# CaravanPi_V2.net
KiCad netlist of a schematic drawn in EAGLE
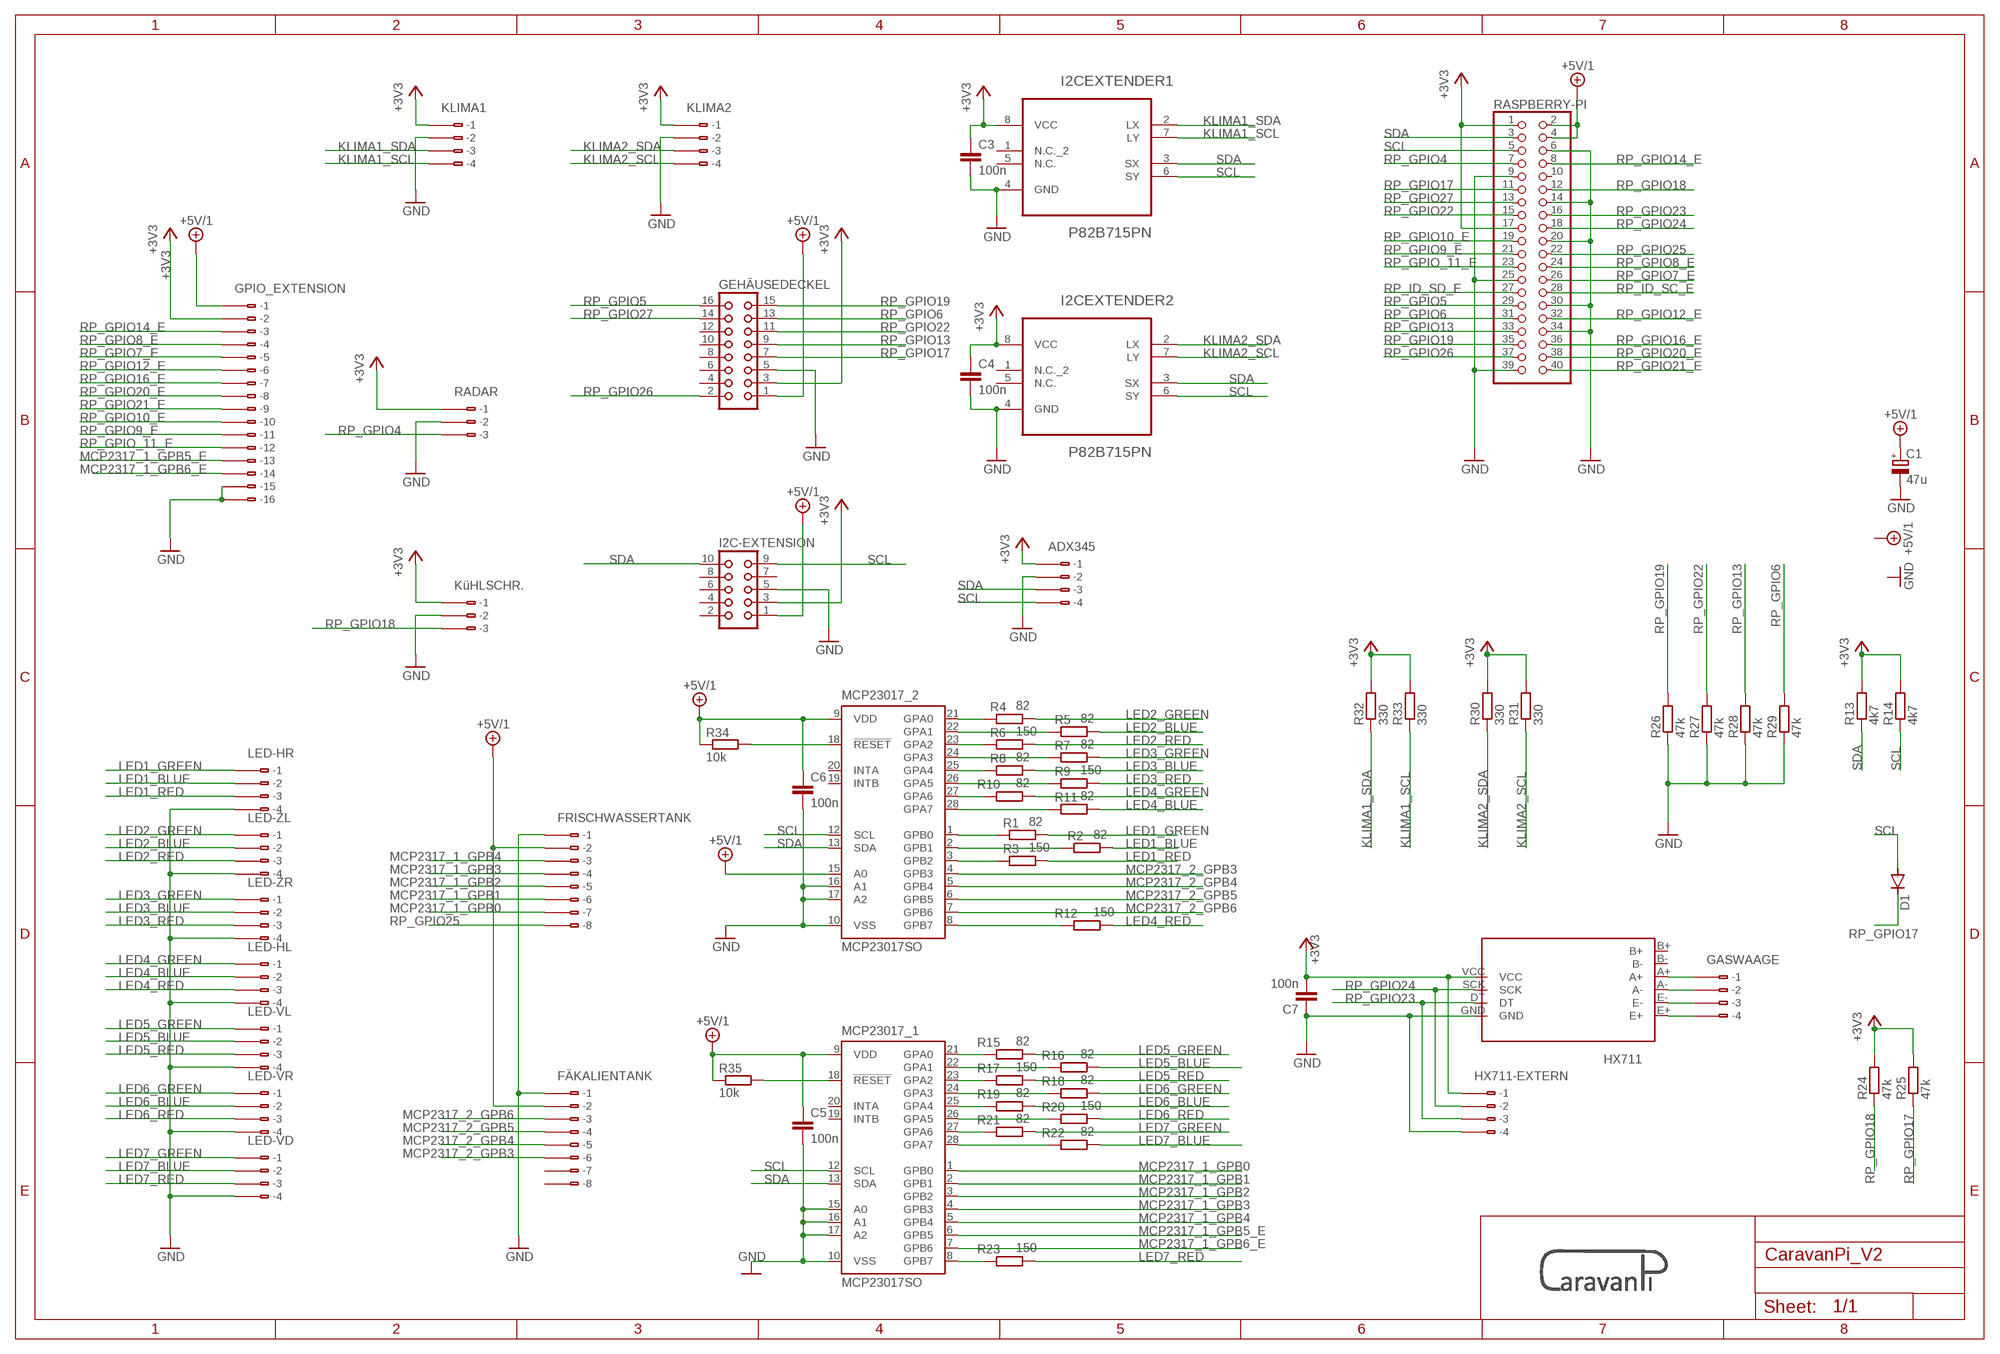
[diagram p0: schematic, sheet 1]

(export (version "E")
  (design (tool "Eeschema 10.0.6"))
  (components
    (comp (ref "ADX345")
      (value "233-404")
      (footprint "eagle-import:233-404")
      (libsource (lib "eagle-import") (part "233-404"))
    )
    (comp (ref "C1")
      (value "47u")
      (footprint "eagle-import:SMC_C")
      (libsource (lib "eagle-import") (part "CPOL-EUSMCC"))
    )
    (comp (ref "C3")
      (value "100n")
      (footprint "eagle-import:C1206")
      (libsource (lib "eagle-import") (part "C-EUC1206"))
    )
    (comp (ref "C4")
      (value "100n")
      (footprint "eagle-import:C1206")
      (libsource (lib "eagle-import") (part "C-EUC1206"))
    )
    (comp (ref "C5")
      (value "100n")
      (footprint "eagle-import:C1206")
      (libsource (lib "eagle-import") (part "C-EUC1206"))
    )
    (comp (ref "C6")
      (value "100n")
      (footprint "eagle-import:C1206")
      (libsource (lib "eagle-import") (part "C-EUC1206"))
    )
    (comp (ref "C7")
      (value "100n")
      (footprint "eagle-import:C1206")
      (libsource (lib "eagle-import") (part "C-EUC1206"))
    )
    (comp (ref "D1")
      (value "DIODE-DO214AC")
      (footprint "eagle-import:DO214AC")
      (libsource (lib "eagle-import") (part "DIODE-DO214AC"))
    )
    (comp (ref "FRISCHWASSERTANK")
      (value "233-408")
      (footprint "eagle-import:233-408")
      (libsource (lib "eagle-import") (part "233-408"))
    )
    (comp (ref "FÄKALIENTANK")
      (value "233-408")
      (footprint "eagle-import:233-408")
      (libsource (lib "eagle-import") (part "233-408"))
    )
    (comp (ref "GASWAAGE")
      (value "233-404")
      (footprint "eagle-import:233-404")
      (libsource (lib "eagle-import") (part "233-404"))
    )
    (comp (ref "GEHÄUSEDECKEL")
      (value "CON16")
      (footprint "eagle-import:CON16")
      (libsource (lib "eagle-import") (part "CON16"))
    )
    (comp (ref "GPIO_EXTENSION")
      (value "233-516")
      (footprint "eagle-import:233-516")
      (fields (field (name "MF") "Wago Corporation") (field (name "MPN") "0233-0516"))
      (libsource (lib "eagle-import") (part "233-516"))
    )
    (comp (ref "HX711")
      (value "HX711A")
      (footprint "eagle-import:HX711")
      (libsource (lib "eagle-import") (part "HX711A"))
    )
    (comp (ref "HX711-EXTERN")
      (value "233-404")
      (footprint "eagle-import:233-404")
      (libsource (lib "eagle-import") (part "233-404"))
    )
    (comp (ref "I2C-EXTENSION")
      (value "CON10")
      (footprint "eagle-import:CON10")
      (libsource (lib "eagle-import") (part "CON10"))
    )
    (comp (ref "I2CEXTENDER1")
      (value "P82B715PN")
      (footprint "eagle-import:DIP254P762X420-8")
      (libsource (lib "eagle-import") (part "P82B715PN"))
    )
    (comp (ref "I2CEXTENDER2")
      (value "P82B715PN")
      (footprint "eagle-import:DIP254P762X420-8")
      (libsource (lib "eagle-import") (part "P82B715PN"))
    )
    (comp (ref "KLIMA1")
      (value "233-404")
      (footprint "eagle-import:233-404")
      (libsource (lib "eagle-import") (part "233-404"))
    )
    (comp (ref "KLIMA2")
      (value "233-404")
      (footprint "eagle-import:233-404")
      (libsource (lib "eagle-import") (part "233-404"))
    )
    (comp (ref "KüHLSCHR.")
      (value "233-403")
      (footprint "eagle-import:233-403")
      (libsource (lib "eagle-import") (part "233-403"))
    )
    (comp (ref "LED-HL")
      (value "233-504")
      (footprint "eagle-import:233-504")
      (fields (field (name "MF") "Wago Corporation") (field (name "MPN") "0233-0504"))
      (libsource (lib "eagle-import") (part "233-504"))
    )
    (comp (ref "LED-HR")
      (value "233-504")
      (footprint "eagle-import:233-504")
      (fields (field (name "MF") "Wago Corporation") (field (name "MPN") "0233-0504"))
      (libsource (lib "eagle-import") (part "233-504"))
    )
    (comp (ref "LED-VD")
      (value "233-504")
      (footprint "eagle-import:233-504")
      (fields (field (name "MF") "Wago Corporation") (field (name "MPN") "0233-0504"))
      (libsource (lib "eagle-import") (part "233-504"))
    )
    (comp (ref "LED-VL")
      (value "233-504")
      (footprint "eagle-import:233-504")
      (fields (field (name "MF") "Wago Corporation") (field (name "MPN") "0233-0504"))
      (libsource (lib "eagle-import") (part "233-504"))
    )
    (comp (ref "LED-VR")
      (value "233-504")
      (footprint "eagle-import:233-504")
      (fields (field (name "MF") "Wago Corporation") (field (name "MPN") "0233-0504"))
      (libsource (lib "eagle-import") (part "233-504"))
    )
    (comp (ref "LED-ZL")
      (value "233-504")
      (footprint "eagle-import:233-504")
      (fields (field (name "MF") "Wago Corporation") (field (name "MPN") "0233-0504"))
      (libsource (lib "eagle-import") (part "233-504"))
    )
    (comp (ref "LED-ZR")
      (value "233-504")
      (footprint "eagle-import:233-504")
      (fields (field (name "MF") "Wago Corporation") (field (name "MPN") "0233-0504"))
      (libsource (lib "eagle-import") (part "233-504"))
    )
    (comp (ref "MCP23017_1")
      (value "MCP23017SO")
      (footprint "eagle-import:SO28W")
      (libsource (lib "eagle-import") (part "MCP23017SO"))
    )
    (comp (ref "MCP23017_2")
      (value "MCP23017SO")
      (footprint "eagle-import:SO28W")
      (libsource (lib "eagle-import") (part "MCP23017SO"))
    )
    (comp (ref "R1")
      (value "82")
      (footprint "eagle-import:M1206")
      (libsource (lib "eagle-import") (part "R-EU_M1206"))
    )
    (comp (ref "R2")
      (value "82")
      (footprint "eagle-import:M1206")
      (libsource (lib "eagle-import") (part "R-EU_M1206"))
    )
    (comp (ref "R3")
      (value "150")
      (footprint "eagle-import:M1206")
      (libsource (lib "eagle-import") (part "R-EU_M1206"))
    )
    (comp (ref "R4")
      (value "82")
      (footprint "eagle-import:M1206")
      (libsource (lib "eagle-import") (part "R-EU_M1206"))
    )
    (comp (ref "R5")
      (value "82")
      (footprint "eagle-import:M1206")
      (libsource (lib "eagle-import") (part "R-EU_M1206"))
    )
    (comp (ref "R6")
      (value "150")
      (footprint "eagle-import:M1206")
      (libsource (lib "eagle-import") (part "R-EU_M1206"))
    )
    (comp (ref "R7")
      (value "82")
      (footprint "eagle-import:M1206")
      (libsource (lib "eagle-import") (part "R-EU_M1206"))
    )
    (comp (ref "R8")
      (value "82")
      (footprint "eagle-import:M1206")
      (libsource (lib "eagle-import") (part "R-EU_M1206"))
    )
    (comp (ref "R9")
      (value "150")
      (footprint "eagle-import:M1206")
      (libsource (lib "eagle-import") (part "R-EU_M1206"))
    )
    (comp (ref "R10")
      (value "82")
      (footprint "eagle-import:M1206")
      (libsource (lib "eagle-import") (part "R-EU_M1206"))
    )
    (comp (ref "R11")
      (value "82")
      (footprint "eagle-import:M1206")
      (libsource (lib "eagle-import") (part "R-EU_M1206"))
    )
    (comp (ref "R12")
      (value "150")
      (footprint "eagle-import:M1206")
      (libsource (lib "eagle-import") (part "R-EU_M1206"))
    )
    (comp (ref "R13")
      (value "4k7")
      (footprint "eagle-import:M1206")
      (libsource (lib "eagle-import") (part "R-EU_M1206"))
    )
    (comp (ref "R14")
      (value "4k7")
      (footprint "eagle-import:M1206")
      (libsource (lib "eagle-import") (part "R-EU_M1206"))
    )
    (comp (ref "R15")
      (value "82")
      (footprint "eagle-import:M1206")
      (libsource (lib "eagle-import") (part "R-EU_M1206"))
    )
    (comp (ref "R16")
      (value "82")
      (footprint "eagle-import:M1206")
      (libsource (lib "eagle-import") (part "R-EU_M1206"))
    )
    (comp (ref "R17")
      (value "150")
      (footprint "eagle-import:M1206")
      (libsource (lib "eagle-import") (part "R-EU_M1206"))
    )
    (comp (ref "R18")
      (value "82")
      (footprint "eagle-import:M1206")
      (libsource (lib "eagle-import") (part "R-EU_M1206"))
    )
    (comp (ref "R19")
      (value "82")
      (footprint "eagle-import:M1206")
      (libsource (lib "eagle-import") (part "R-EU_M1206"))
    )
    (comp (ref "R20")
      (value "150")
      (footprint "eagle-import:M1206")
      (libsource (lib "eagle-import") (part "R-EU_M1206"))
    )
    (comp (ref "R21")
      (value "82")
      (footprint "eagle-import:M1206")
      (libsource (lib "eagle-import") (part "R-EU_M1206"))
    )
    (comp (ref "R22")
      (value "82")
      (footprint "eagle-import:M1206")
      (libsource (lib "eagle-import") (part "R-EU_M1206"))
    )
    (comp (ref "R23")
      (value "150")
      (footprint "eagle-import:M1206")
      (libsource (lib "eagle-import") (part "R-EU_M1206"))
    )
    (comp (ref "R24")
      (value "47k")
      (footprint "eagle-import:M1206")
      (libsource (lib "eagle-import") (part "R-EU_M1206"))
    )
    (comp (ref "R25")
      (value "47k")
      (footprint "eagle-import:M1206")
      (libsource (lib "eagle-import") (part "R-EU_M1206"))
    )
    (comp (ref "R26")
      (value "47k")
      (footprint "eagle-import:M1206")
      (libsource (lib "eagle-import") (part "R-EU_M1206"))
    )
    (comp (ref "R27")
      (value "47k")
      (footprint "eagle-import:M1206")
      (libsource (lib "eagle-import") (part "R-EU_M1206"))
    )
    (comp (ref "R28")
      (value "47k")
      (footprint "eagle-import:M1206")
      (libsource (lib "eagle-import") (part "R-EU_M1206"))
    )
    (comp (ref "R29")
      (value "47k")
      (footprint "eagle-import:M1206")
      (libsource (lib "eagle-import") (part "R-EU_M1206"))
    )
    (comp (ref "R30")
      (value "330")
      (footprint "eagle-import:M1206")
      (libsource (lib "eagle-import") (part "R-EU_M1206"))
    )
    (comp (ref "R31")
      (value "330")
      (footprint "eagle-import:M1206")
      (libsource (lib "eagle-import") (part "R-EU_M1206"))
    )
    (comp (ref "R32")
      (value "330")
      (footprint "eagle-import:M1206")
      (libsource (lib "eagle-import") (part "R-EU_M1206"))
    )
    (comp (ref "R33")
      (value "330")
      (footprint "eagle-import:M1206")
      (libsource (lib "eagle-import") (part "R-EU_M1206"))
    )
    (comp (ref "R34")
      (value "10k")
      (footprint "eagle-import:M1206")
      (libsource (lib "eagle-import") (part "R-EU_M1206"))
    )
    (comp (ref "R35")
      (value "10k")
      (footprint "eagle-import:M1206")
      (libsource (lib "eagle-import") (part "R-EU_M1206"))
    )
    (comp (ref "RADAR")
      (value "233-403")
      (footprint "eagle-import:233-403")
      (libsource (lib "eagle-import") (part "233-403"))
    )
    (comp (ref "RASPBERRY-PI")
      (value "PINHD-2X20")
      (footprint "eagle-import:2X20")
      (libsource (lib "eagle-import") (part "PINHD-2X20"))
    )
    (comp (ref "U$1")
      (value "CARAVAN_PI_LOGO")
      (footprint "eagle-import:CARAVAN_PI_LOGO")
      (libsource (lib "eagle-import") (part "CARAVAN_PI_LOGO"))
    )
  )
  (nets
    (net (code "1") (name "+3V3") (class "Default")
      (node (ref "ADX345") (pin "B1") (pinfunction "B-1_B1") (pintype "passive"))
      (node (ref "C3") (pin "1") (pinfunction "1_1") (pintype "passive"))
      (node (ref "C4") (pin "1") (pinfunction "1_1") (pintype "passive"))
      (node (ref "C7") (pin "2") (pinfunction "2_2") (pintype "passive"))
      (node (ref "GEHÄUSEDECKEL") (pin "3") (pinfunction "3_3") (pintype "passive"))
      (node (ref "GPIO_EXTENSION") (pin "B2") (pinfunction "B-2_B2") (pintype "passive"))
      (node (ref "HX711") (pin "VCC") (pinfunction "VCC_VCC") (pintype "bidirectional"))
      (node (ref "HX711-EXTERN") (pin "B1") (pinfunction "B-1_B1") (pintype "passive"))
      (node (ref "I2C-EXTENSION") (pin "3") (pinfunction "3_3") (pintype "passive"))
      (node (ref "I2CEXTENDER1") (pin "8") (pinfunction "VCC_8") (pintype "power_in"))
      (node (ref "I2CEXTENDER2") (pin "8") (pinfunction "VCC_8") (pintype "power_in"))
      (node (ref "KLIMA1") (pin "B1") (pinfunction "B-1_B1") (pintype "passive"))
      (node (ref "KLIMA2") (pin "B1") (pinfunction "B-1_B1") (pintype "passive"))
      (node (ref "KüHLSCHR.") (pin "B1") (pinfunction "B-1_B1") (pintype "passive"))
      (node (ref "R13") (pin "2") (pinfunction "2_2") (pintype "passive"))
      (node (ref "R14") (pin "2") (pinfunction "2_2") (pintype "passive"))
      (node (ref "R24") (pin "2") (pinfunction "2_2") (pintype "passive"))
      (node (ref "R25") (pin "2") (pinfunction "2_2") (pintype "passive"))
      (node (ref "R30") (pin "2") (pinfunction "2_2") (pintype "passive"))
      (node (ref "R31") (pin "2") (pinfunction "2_2") (pintype "passive"))
      (node (ref "R32") (pin "2") (pinfunction "2_2") (pintype "passive"))
      (node (ref "R33") (pin "2") (pinfunction "2_2") (pintype "passive"))
      (node (ref "RADAR") (pin "B1") (pinfunction "B-1_B1") (pintype "passive"))
      (node (ref "RASPBERRY-PI") (pin "1") (pinfunction "1_1") (pintype "passive"))
      (node (ref "RASPBERRY-PI") (pin "17") (pinfunction "17_17") (pintype "passive"))
    )
    (net (code "2") (name "+5V{slash}1") (class "Default")
      (node (ref "C1") (pin "+") (pinfunction "+_+") (pintype "passive"))
      (node (ref "C5") (pin "1") (pinfunction "1_1") (pintype "passive"))
      (node (ref "C6") (pin "1") (pinfunction "1_1") (pintype "passive"))
      (node (ref "FRISCHWASSERTANK") (pin "B2") (pinfunction "B-2_B2") (pintype "passive"))
      (node (ref "FÄKALIENTANK") (pin "B2") (pinfunction "B-2_B2") (pintype "passive"))
      (node (ref "GEHÄUSEDECKEL") (pin "1") (pinfunction "1_1") (pintype "passive"))
      (node (ref "GPIO_EXTENSION") (pin "B1") (pinfunction "B-1_B1") (pintype "passive"))
      (node (ref "I2C-EXTENSION") (pin "1") (pinfunction "1_1") (pintype "passive"))
      (node (ref "MCP23017_1") (pin "9") (pinfunction "VDD_9") (pintype "power_in"))
      (node (ref "MCP23017_2") (pin "15") (pinfunction "A0_15") (pintype "input"))
      (node (ref "MCP23017_2") (pin "9") (pinfunction "VDD_9") (pintype "power_in"))
      (node (ref "R34") (pin "1") (pinfunction "1_1") (pintype "passive"))
      (node (ref "R35") (pin "1") (pinfunction "1_1") (pintype "passive"))
      (node (ref "RASPBERRY-PI") (pin "2") (pinfunction "2_2") (pintype "passive"))
      (node (ref "RASPBERRY-PI") (pin "4") (pinfunction "4_4") (pintype "passive"))
    )
    (net (code "3") (name "/KLIMA1_SCL") (class "Default")
      (node (ref "I2CEXTENDER1") (pin "7") (pinfunction "LY_7") (pintype "bidirectional"))
      (node (ref "KLIMA1") (pin "B4") (pinfunction "B-4_B4") (pintype "passive"))
      (node (ref "R33") (pin "1") (pinfunction "1_1") (pintype "passive"))
    )
    (net (code "4") (name "/KLIMA1_SDA") (class "Default")
      (node (ref "I2CEXTENDER1") (pin "2") (pinfunction "LX_2") (pintype "bidirectional"))
      (node (ref "KLIMA1") (pin "B3") (pinfunction "B-3_B3") (pintype "passive"))
      (node (ref "R32") (pin "1") (pinfunction "1_1") (pintype "passive"))
    )
    (net (code "5") (name "/KLIMA2_SCL") (class "Default")
      (node (ref "I2CEXTENDER2") (pin "7") (pinfunction "LY_7") (pintype "bidirectional"))
      (node (ref "KLIMA2") (pin "B4") (pinfunction "B-4_B4") (pintype "passive"))
      (node (ref "R31") (pin "1") (pinfunction "1_1") (pintype "passive"))
    )
    (net (code "6") (name "/KLIMA2_SDA") (class "Default")
      (node (ref "I2CEXTENDER2") (pin "2") (pinfunction "LX_2") (pintype "bidirectional"))
      (node (ref "KLIMA2") (pin "B3") (pinfunction "B-3_B3") (pintype "passive"))
      (node (ref "R30") (pin "1") (pinfunction "1_1") (pintype "passive"))
    )
    (net (code "7") (name "/LED1_BLUE") (class "Default")
      (node (ref "LED-HR") (pin "B2") (pinfunction "B-2_B2") (pintype "passive"))
      (node (ref "R2") (pin "2") (pinfunction "2_2") (pintype "passive"))
    )
    (net (code "8") (name "/LED1_GREEN") (class "Default")
      (node (ref "LED-HR") (pin "B1") (pinfunction "B-1_B1") (pintype "passive"))
      (node (ref "R1") (pin "2") (pinfunction "2_2") (pintype "passive"))
    )
    (net (code "9") (name "/LED1_RED") (class "Default")
      (node (ref "LED-HR") (pin "B3") (pinfunction "B-3_B3") (pintype "passive"))
      (node (ref "R3") (pin "2") (pinfunction "2_2") (pintype "passive"))
    )
    (net (code "10") (name "/LED2_BLUE") (class "Default")
      (node (ref "LED-ZL") (pin "B2") (pinfunction "B-2_B2") (pintype "passive"))
      (node (ref "R5") (pin "2") (pinfunction "2_2") (pintype "passive"))
    )
    (net (code "11") (name "/LED2_GREEN") (class "Default")
      (node (ref "LED-ZL") (pin "B1") (pinfunction "B-1_B1") (pintype "passive"))
      (node (ref "R4") (pin "2") (pinfunction "2_2") (pintype "passive"))
    )
    (net (code "12") (name "/LED2_RED") (class "Default")
      (node (ref "LED-ZL") (pin "B3") (pinfunction "B-3_B3") (pintype "passive"))
      (node (ref "R6") (pin "2") (pinfunction "2_2") (pintype "passive"))
    )
    (net (code "13") (name "/LED3_BLUE") (class "Default")
      (node (ref "LED-ZR") (pin "B2") (pinfunction "B-2_B2") (pintype "passive"))
      (node (ref "R8") (pin "2") (pinfunction "2_2") (pintype "passive"))
    )
    (net (code "14") (name "/LED3_GREEN") (class "Default")
      (node (ref "LED-ZR") (pin "B1") (pinfunction "B-1_B1") (pintype "passive"))
      (node (ref "R7") (pin "2") (pinfunction "2_2") (pintype "passive"))
    )
    (net (code "15") (name "/LED3_RED") (class "Default")
      (node (ref "LED-ZR") (pin "B3") (pinfunction "B-3_B3") (pintype "passive"))
      (node (ref "R9") (pin "2") (pinfunction "2_2") (pintype "passive"))
    )
    (net (code "16") (name "/LED4_BLUE") (class "Default")
      (node (ref "LED-HL") (pin "B2") (pinfunction "B-2_B2") (pintype "passive"))
      (node (ref "R11") (pin "2") (pinfunction "2_2") (pintype "passive"))
    )
    (net (code "17") (name "/LED4_GREEN") (class "Default")
      (node (ref "LED-HL") (pin "B1") (pinfunction "B-1_B1") (pintype "passive"))
      (node (ref "R10") (pin "2") (pinfunction "2_2") (pintype "passive"))
    )
    (net (code "18") (name "/LED4_RED") (class "Default")
      (node (ref "LED-HL") (pin "B3") (pinfunction "B-3_B3") (pintype "passive"))
      (node (ref "R12") (pin "2") (pinfunction "2_2") (pintype "passive"))
    )
    (net (code "19") (name "/LED5_BLUE") (class "Default")
      (node (ref "LED-VL") (pin "B2") (pinfunction "B-2_B2") (pintype "passive"))
      (node (ref "R16") (pin "2") (pinfunction "2_2") (pintype "passive"))
    )
    (net (code "20") (name "/LED5_GREEN") (class "Default")
      (node (ref "LED-VL") (pin "B1") (pinfunction "B-1_B1") (pintype "passive"))
      (node (ref "R15") (pin "2") (pinfunction "2_2") (pintype "passive"))
    )
    (net (code "21") (name "/LED5_RED") (class "Default")
      (node (ref "LED-VL") (pin "B3") (pinfunction "B-3_B3") (pintype "passive"))
      (node (ref "R17") (pin "2") (pinfunction "2_2") (pintype "passive"))
    )
    (net (code "22") (name "/LED6_BLUE") (class "Default")
      (node (ref "LED-VR") (pin "B2") (pinfunction "B-2_B2") (pintype "passive"))
      (node (ref "R19") (pin "2") (pinfunction "2_2") (pintype "passive"))
    )
    (net (code "23") (name "/LED6_GREEN") (class "Default")
      (node (ref "LED-VR") (pin "B1") (pinfunction "B-1_B1") (pintype "passive"))
      (node (ref "R18") (pin "2") (pinfunction "2_2") (pintype "passive"))
    )
    (net (code "24") (name "/LED6_RED") (class "Default")
      (node (ref "LED-VR") (pin "B3") (pinfunction "B-3_B3") (pintype "passive"))
      (node (ref "R20") (pin "2") (pinfunction "2_2") (pintype "passive"))
    )
    (net (code "25") (name "/LED7_BLUE") (class "Default")
      (node (ref "LED-VD") (pin "B2") (pinfunction "B-2_B2") (pintype "passive"))
      (node (ref "R22") (pin "2") (pinfunction "2_2") (pintype "passive"))
    )
    (net (code "26") (name "/LED7_GREEN") (class "Default")
      (node (ref "LED-VD") (pin "B1") (pinfunction "B-1_B1") (pintype "passive"))
      (node (ref "R21") (pin "2") (pinfunction "2_2") (pintype "passive"))
    )
    (net (code "27") (name "/LED7_RED") (class "Default")
      (node (ref "LED-VD") (pin "B3") (pinfunction "B-3_B3") (pintype "passive"))
      (node (ref "R23") (pin "2") (pinfunction "2_2") (pintype "passive"))
    )
    (net (code "28") (name "/MCP2317_1_GPB0") (class "Default")
      (node (ref "FRISCHWASSERTANK") (pin "B7") (pinfunction "B-7_B7") (pintype "passive"))
      (node (ref "MCP23017_1") (pin "1") (pinfunction "GPB0_1") (pintype "bidirectional"))
    )
    (net (code "29") (name "/MCP2317_1_GPB1") (class "Default")
      (node (ref "FRISCHWASSERTANK") (pin "B6") (pinfunction "B-6_B6") (pintype "passive"))
      (node (ref "MCP23017_1") (pin "2") (pinfunction "GPB1_2") (pintype "bidirectional"))
    )
    (net (code "30") (name "/MCP2317_1_GPB2") (class "Default")
      (node (ref "FRISCHWASSERTANK") (pin "B5") (pinfunction "B-5_B5") (pintype "passive"))
      (node (ref "MCP23017_1") (pin "3") (pinfunction "GPB2_3") (pintype "bidirectional"))
    )
    (net (code "31") (name "/MCP2317_1_GPB3") (class "Default")
      (node (ref "FRISCHWASSERTANK") (pin "B4") (pinfunction "B-4_B4") (pintype "passive"))
      (node (ref "MCP23017_1") (pin "4") (pinfunction "GPB3_4") (pintype "bidirectional"))
    )
    (net (code "32") (name "/MCP2317_1_GPB4") (class "Default")
      (node (ref "FRISCHWASSERTANK") (pin "B3") (pinfunction "B-3_B3") (pintype "passive"))
      (node (ref "MCP23017_1") (pin "5") (pinfunction "GPB4_5") (pintype "bidirectional"))
    )
    (net (code "33") (name "/MCP2317_1_GPB5_E") (class "Default")
      (node (ref "GPIO_EXTENSION") (pin "B13") (pinfunction "B-13_B13") (pintype "passive"))
      (node (ref "MCP23017_1") (pin "6") (pinfunction "GPB5_6") (pintype "bidirectional"))
    )
    (net (code "34") (name "/MCP2317_1_GPB6_E") (class "Default")
      (node (ref "GPIO_EXTENSION") (pin "B14") (pinfunction "B-14_B14") (pintype "passive"))
      (node (ref "MCP23017_1") (pin "7") (pinfunction "GPB6_7") (pintype "bidirectional"))
    )
    (net (code "35") (name "/MCP2317_2_GPB3") (class "Default")
      (node (ref "FÄKALIENTANK") (pin "B6") (pinfunction "B-6_B6") (pintype "passive"))
      (node (ref "MCP23017_2") (pin "4") (pinfunction "GPB3_4") (pintype "bidirectional"))
    )
    (net (code "36") (name "/MCP2317_2_GPB4") (class "Default")
      (node (ref "FÄKALIENTANK") (pin "B5") (pinfunction "B-5_B5") (pintype "passive"))
      (node (ref "MCP23017_2") (pin "5") (pinfunction "GPB4_5") (pintype "bidirectional"))
    )
    (net (code "37") (name "/MCP2317_2_GPB5") (class "Default")
      (node (ref "FÄKALIENTANK") (pin "B4") (pinfunction "B-4_B4") (pintype "passive"))
      (node (ref "MCP23017_2") (pin "6") (pinfunction "GPB5_6") (pintype "bidirectional"))
    )
    (net (code "38") (name "/MCP2317_2_GPB6") (class "Default")
      (node (ref "FÄKALIENTANK") (pin "B3") (pinfunction "B-3_B3") (pintype "passive"))
      (node (ref "MCP23017_2") (pin "7") (pinfunction "GPB6_7") (pintype "bidirectional"))
    )
    (net (code "39") (name "/RP_GPIO4") (class "Default")
      (node (ref "RADAR") (pin "B3") (pinfunction "B-3_B3") (pintype "passive"))
      (node (ref "RASPBERRY-PI") (pin "7") (pinfunction "7_7") (pintype "passive"))
    )
    (net (code "40") (name "/RP_GPIO5") (class "Default")
      (node (ref "GEHÄUSEDECKEL") (pin "16") (pinfunction "16_16") (pintype "passive"))
      (node (ref "RASPBERRY-PI") (pin "29") (pinfunction "29_29") (pintype "passive"))
    )
    (net (code "41") (name "/RP_GPIO6") (class "Default")
      (node (ref "GEHÄUSEDECKEL") (pin "13") (pinfunction "13_13") (pintype "passive"))
      (node (ref "R29") (pin "2") (pinfunction "2_2") (pintype "passive"))
      (node (ref "RASPBERRY-PI") (pin "31") (pinfunction "31_31") (pintype "passive"))
    )
    (net (code "42") (name "/RP_GPIO7_E") (class "Default")
      (node (ref "GPIO_EXTENSION") (pin "B5") (pinfunction "B-5_B5") (pintype "passive"))
      (node (ref "RASPBERRY-PI") (pin "26") (pinfunction "26_26") (pintype "passive"))
    )
    (net (code "43") (name "/RP_GPIO8_E") (class "Default")
      (node (ref "GPIO_EXTENSION") (pin "B4") (pinfunction "B-4_B4") (pintype "passive"))
      (node (ref "RASPBERRY-PI") (pin "24") (pinfunction "24_24") (pintype "passive"))
    )
    (net (code "44") (name "/RP_GPIO9_E") (class "Default")
      (node (ref "GPIO_EXTENSION") (pin "B11") (pinfunction "B-11_B11") (pintype "passive"))
      (node (ref "RASPBERRY-PI") (pin "21") (pinfunction "21_21") (pintype "passive"))
    )
    (net (code "45") (name "/RP_GPIO10_E") (class "Default")
      (node (ref "GPIO_EXTENSION") (pin "B10") (pinfunction "B-10_B10") (pintype "passive"))
      (node (ref "RASPBERRY-PI") (pin "19") (pinfunction "19_19") (pintype "passive"))
    )
    (net (code "46") (name "/RP_GPIO12_E") (class "Default")
      (node (ref "GPIO_EXTENSION") (pin "B6") (pinfunction "B-6_B6") (pintype "passive"))
      (node (ref "RASPBERRY-PI") (pin "32") (pinfunction "32_32") (pintype "passive"))
    )
    (net (code "47") (name "/RP_GPIO13") (class "Default")
      (node (ref "GEHÄUSEDECKEL") (pin "9") (pinfunction "9_9") (pintype "passive"))
      (node (ref "R28") (pin "2") (pinfunction "2_2") (pintype "passive"))
      (node (ref "RASPBERRY-PI") (pin "33") (pinfunction "33_33") (pintype "passive"))
    )
    (net (code "48") (name "/RP_GPIO14_E") (class "Default")
      (node (ref "GPIO_EXTENSION") (pin "B3") (pinfunction "B-3_B3") (pintype "passive"))
      (node (ref "RASPBERRY-PI") (pin "8") (pinfunction "8_8") (pintype "passive"))
    )
    (net (code "49") (name "/RP_GPIO16_E") (class "Default")
      (node (ref "GPIO_EXTENSION") (pin "B7") (pinfunction "B-7_B7") (pintype "passive"))
      (node (ref "RASPBERRY-PI") (pin "36") (pinfunction "36_36") (pintype "passive"))
    )
    (net (code "50") (name "/RP_GPIO17") (class "Default")
      (node (ref "D1") (pin "C") (pinfunction "C_C") (pintype "passive"))
      (node (ref "GEHÄUSEDECKEL") (pin "7") (pinfunction "7_7") (pintype "passive"))
      (node (ref "R25") (pin "1") (pinfunction "1_1") (pintype "passive"))
      (node (ref "RASPBERRY-PI") (pin "11") (pinfunction "11_11") (pintype "passive"))
    )
    (net (code "51") (name "/RP_GPIO18") (class "Default")
      (node (ref "KüHLSCHR.") (pin "B3") (pinfunction "B-3_B3") (pintype "passive"))
      (node (ref "R24") (pin "1") (pinfunction "1_1") (pintype "passive"))
      (node (ref "RASPBERRY-PI") (pin "12") (pinfunction "12_12") (pintype "passive"))
    )
    (net (code "52") (name "/RP_GPIO19") (class "Default")
      (node (ref "GEHÄUSEDECKEL") (pin "15") (pinfunction "15_15") (pintype "passive"))
      (node (ref "R26") (pin "2") (pinfunction "2_2") (pintype "passive"))
      (node (ref "RASPBERRY-PI") (pin "35") (pinfunction "35_35") (pintype "passive"))
    )
    (net (code "53") (name "/RP_GPIO20_E") (class "Default")
      (node (ref "GPIO_EXTENSION") (pin "B8") (pinfunction "B-8_B8") (pintype "passive"))
      (node (ref "RASPBERRY-PI") (pin "38") (pinfunction "38_38") (pintype "passive"))
    )
    (net (code "54") (name "/RP_GPIO21_E") (class "Default")
      (node (ref "GPIO_EXTENSION") (pin "B9") (pinfunction "B-9_B9") (pintype "passive"))
      (node (ref "RASPBERRY-PI") (pin "40") (pinfunction "40_40") (pintype "passive"))
    )
    (net (code "55") (name "/RP_GPIO22") (class "Default")
      (node (ref "GEHÄUSEDECKEL") (pin "11") (pinfunction "11_11") (pintype "passive"))
      (node (ref "R27") (pin "2") (pinfunction "2_2") (pintype "passive"))
      (node (ref "RASPBERRY-PI") (pin "15") (pinfunction "15_15") (pintype "passive"))
    )
    (net (code "56") (name "/RP_GPIO23") (class "Default")
      (node (ref "HX711") (pin "DT") (pinfunction "DT_DT") (pintype "bidirectional"))
      (node (ref "HX711-EXTERN") (pin "B3") (pinfunction "B-3_B3") (pintype "passive"))
      (node (ref "RASPBERRY-PI") (pin "16") (pinfunction "16_16") (pintype "passive"))
    )
    (net (code "57") (name "/RP_GPIO24") (class "Default")
      (node (ref "HX711") (pin "SCK") (pinfunction "SCK_SCK") (pintype "bidirectional"))
      (node (ref "HX711-EXTERN") (pin "B2") (pinfunction "B-2_B2") (pintype "passive"))
      (node (ref "RASPBERRY-PI") (pin "18") (pinfunction "18_18") (pintype "passive"))
    )
    (net (code "58") (name "/RP_GPIO25") (class "Default")
      (node (ref "FRISCHWASSERTANK") (pin "B8") (pinfunction "B-8_B8") (pintype "passive"))
      (node (ref "RASPBERRY-PI") (pin "22") (pinfunction "22_22") (pintype "passive"))
    )
    (net (code "59") (name "/RP_GPIO26") (class "Default")
      (node (ref "GEHÄUSEDECKEL") (pin "2") (pinfunction "2_2") (pintype "passive"))
      (node (ref "RASPBERRY-PI") (pin "37") (pinfunction "37_37") (pintype "passive"))
    )
    (net (code "60") (name "/RP_GPIO27") (class "Default")
      (node (ref "GEHÄUSEDECKEL") (pin "14") (pinfunction "14_14") (pintype "passive"))
      (node (ref "RASPBERRY-PI") (pin "13") (pinfunction "13_13") (pintype "passive"))
    )
    (net (code "61") (name "/RP_GPIO_11_E") (class "Default")
      (node (ref "GPIO_EXTENSION") (pin "B12") (pinfunction "B-12_B12") (pintype "passive"))
      (node (ref "RASPBERRY-PI") (pin "23") (pinfunction "23_23") (pintype "passive"))
    )
    (net (code "62") (name "/RP_ID_SC_E") (class "Default")
      (node (ref "RASPBERRY-PI") (pin "28") (pinfunction "28_28") (pintype "passive"))
    )
    (net (code "63") (name "/RP_ID_SD_E") (class "Default")
      (node (ref "RASPBERRY-PI") (pin "27") (pinfunction "27_27") (pintype "passive"))
    )
    (net (code "64") (name "/SCL") (class "Default")
      (node (ref "ADX345") (pin "B4") (pinfunction "B-4_B4") (pintype "passive"))
      (node (ref "D1") (pin "A") (pinfunction "A_A") (pintype "passive"))
      (node (ref "I2C-EXTENSION") (pin "9") (pinfunction "9_9") (pintype "passive"))
      (node (ref "I2CEXTENDER1") (pin "6") (pinfunction "SY_6") (pintype "bidirectional"))
      (node (ref "I2CEXTENDER2") (pin "6") (pinfunction "SY_6") (pintype "bidirectional"))
      (node (ref "MCP23017_1") (pin "12") (pinfunction "SCL_12") (pintype "input"))
      (node (ref "MCP23017_2") (pin "12") (pinfunction "SCL_12") (pintype "input"))
      (node (ref "R14") (pin "1") (pinfunction "1_1") (pintype "passive"))
      (node (ref "RASPBERRY-PI") (pin "5") (pinfunction "5_5") (pintype "passive"))
    )
    (net (code "65") (name "/SDA") (class "Default")
      (node (ref "ADX345") (pin "B3") (pinfunction "B-3_B3") (pintype "passive"))
      (node (ref "I2C-EXTENSION") (pin "10") (pinfunction "10_10") (pintype "passive"))
      (node (ref "I2CEXTENDER1") (pin "3") (pinfunction "SX_3") (pintype "bidirectional"))
      (node (ref "I2CEXTENDER2") (pin "3") (pinfunction "SX_3") (pintype "bidirectional"))
      (node (ref "MCP23017_1") (pin "13") (pinfunction "SDA_13") (pintype "bidirectional"))
      (node (ref "MCP23017_2") (pin "13") (pinfunction "SDA_13") (pintype "bidirectional"))
      (node (ref "R13") (pin "1") (pinfunction "1_1") (pintype "passive"))
      (node (ref "RASPBERRY-PI") (pin "3") (pinfunction "3_3") (pintype "passive"))
    )
    (net (code "66") (name "GND") (class "Default")
      (node (ref "ADX345") (pin "B2") (pinfunction "B-2_B2") (pintype "passive"))
      (node (ref "C1") (pin "-") (pinfunction "-_-") (pintype "passive"))
      (node (ref "C3") (pin "2") (pinfunction "2_2") (pintype "passive"))
      (node (ref "C4") (pin "2") (pinfunction "2_2") (pintype "passive"))
      (node (ref "C5") (pin "2") (pinfunction "2_2") (pintype "passive"))
      (node (ref "C6") (pin "2") (pinfunction "2_2") (pintype "passive"))
      (node (ref "C7") (pin "1") (pinfunction "1_1") (pintype "passive"))
      (node (ref "FRISCHWASSERTANK") (pin "B1") (pinfunction "B-1_B1") (pintype "passive"))
      (node (ref "FÄKALIENTANK") (pin "B1") (pinfunction "B-1_B1") (pintype "passive"))
      (node (ref "GEHÄUSEDECKEL") (pin "5") (pinfunction "5_5") (pintype "passive"))
      (node (ref "GPIO_EXTENSION") (pin "B15") (pinfunction "B-15_B15") (pintype "passive"))
      (node (ref "GPIO_EXTENSION") (pin "B16") (pinfunction "B-16_B16") (pintype "passive"))
      (node (ref "HX711") (pin "GND") (pinfunction "GND_GND") (pintype "bidirectional"))
      (node (ref "HX711-EXTERN") (pin "B4") (pinfunction "B-4_B4") (pintype "passive"))
      (node (ref "I2C-EXTENSION") (pin "5") (pinfunction "5_5") (pintype "passive"))
      (node (ref "I2CEXTENDER1") (pin "4") (pinfunction "GND_4") (pintype "passive"))
      (node (ref "I2CEXTENDER2") (pin "4") (pinfunction "GND_4") (pintype "passive"))
      (node (ref "KLIMA1") (pin "B2") (pinfunction "B-2_B2") (pintype "passive"))
      (node (ref "KLIMA2") (pin "B2") (pinfunction "B-2_B2") (pintype "passive"))
      (node (ref "KüHLSCHR.") (pin "B2") (pinfunction "B-2_B2") (pintype "passive"))
      (node (ref "LED-HL") (pin "B4") (pinfunction "B-4_B4") (pintype "passive"))
      (node (ref "LED-HR") (pin "B4") (pinfunction "B-4_B4") (pintype "passive"))
      (node (ref "LED-VD") (pin "B4") (pinfunction "B-4_B4") (pintype "passive"))
      (node (ref "LED-VL") (pin "B4") (pinfunction "B-4_B4") (pintype "passive"))
      (node (ref "LED-VR") (pin "B4") (pinfunction "B-4_B4") (pintype "passive"))
      (node (ref "LED-ZL") (pin "B4") (pinfunction "B-4_B4") (pintype "passive"))
      (node (ref "LED-ZR") (pin "B4") (pinfunction "B-4_B4") (pintype "passive"))
      (node (ref "MCP23017_1") (pin "10") (pinfunction "VSS_10") (pintype "power_in"))
      (node (ref "MCP23017_1") (pin "15") (pinfunction "A0_15") (pintype "input"))
      (node (ref "MCP23017_1") (pin "16") (pinfunction "A1_16") (pintype "input"))
      (node (ref "MCP23017_1") (pin "17") (pinfunction "A2_17") (pintype "input"))
      (node (ref "MCP23017_2") (pin "10") (pinfunction "VSS_10") (pintype "power_in"))
      (node (ref "MCP23017_2") (pin "16") (pinfunction "A1_16") (pintype "input"))
      (node (ref "MCP23017_2") (pin "17") (pinfunction "A2_17") (pintype "input"))
      (node (ref "R26") (pin "1") (pinfunction "1_1") (pintype "passive"))
      (node (ref "R27") (pin "1") (pinfunction "1_1") (pintype "passive"))
      (node (ref "R28") (pin "1") (pinfunction "1_1") (pintype "passive"))
      (node (ref "R29") (pin "1") (pinfunction "1_1") (pintype "passive"))
      (node (ref "RADAR") (pin "B2") (pinfunction "B-2_B2") (pintype "passive"))
      (node (ref "RASPBERRY-PI") (pin "14") (pinfunction "14_14") (pintype "passive"))
      (node (ref "RASPBERRY-PI") (pin "20") (pinfunction "20_20") (pintype "passive"))
      (node (ref "RASPBERRY-PI") (pin "25") (pinfunction "25_25") (pintype "passive"))
      (node (ref "RASPBERRY-PI") (pin "30") (pinfunction "30_30") (pintype "passive"))
      (node (ref "RASPBERRY-PI") (pin "34") (pinfunction "34_34") (pintype "passive"))
      (node (ref "RASPBERRY-PI") (pin "39") (pinfunction "39_39") (pintype "passive"))
      (node (ref "RASPBERRY-PI") (pin "6") (pinfunction "6_6") (pintype "passive"))
      (node (ref "RASPBERRY-PI") (pin "9") (pinfunction "9_9") (pintype "passive"))
    )
    (net (code "67") (name "Net-(GASWAAGE-B-1)") (class "Default")
      (node (ref "GASWAAGE") (pin "B1") (pinfunction "B-1_B1") (pintype "passive"))
      (node (ref "HX711") (pin "A+") (pinfunction "A+_A+") (pintype "bidirectional"))
    )
    (net (code "68") (name "Net-(GASWAAGE-B-2)") (class "Default")
      (node (ref "GASWAAGE") (pin "B2") (pinfunction "B-2_B2") (pintype "passive"))
      (node (ref "HX711") (pin "A-") (pinfunction "A-_A-") (pintype "bidirectional"))
    )
    (net (code "69") (name "Net-(GASWAAGE-B-3)") (class "Default")
      (node (ref "GASWAAGE") (pin "B3") (pinfunction "B-3_B3") (pintype "passive"))
      (node (ref "HX711") (pin "E-") (pinfunction "E-_E-") (pintype "bidirectional"))
    )
    (net (code "70") (name "Net-(GASWAAGE-B-4)") (class "Default")
      (node (ref "GASWAAGE") (pin "B4") (pinfunction "B-4_B4") (pintype "passive"))
      (node (ref "HX711") (pin "E+") (pinfunction "E+_E+") (pintype "bidirectional"))
    )
    (net (code "71") (name "Net-(MCP23017_1-GPA0)") (class "Default")
      (node (ref "MCP23017_1") (pin "21") (pinfunction "GPA0_21") (pintype "bidirectional"))
      (node (ref "R15") (pin "1") (pinfunction "1_1") (pintype "passive"))
    )
    (net (code "72") (name "Net-(MCP23017_1-GPA1)") (class "Default")
      (node (ref "MCP23017_1") (pin "22") (pinfunction "GPA1_22") (pintype "bidirectional"))
      (node (ref "R16") (pin "1") (pinfunction "1_1") (pintype "passive"))
    )
    (net (code "73") (name "Net-(MCP23017_1-GPA2)") (class "Default")
      (node (ref "MCP23017_1") (pin "23") (pinfunction "GPA2_23") (pintype "bidirectional"))
      (node (ref "R17") (pin "1") (pinfunction "1_1") (pintype "passive"))
    )
    (net (code "74") (name "Net-(MCP23017_1-GPA3)") (class "Default")
      (node (ref "MCP23017_1") (pin "24") (pinfunction "GPA3_24") (pintype "bidirectional"))
      (node (ref "R18") (pin "1") (pinfunction "1_1") (pintype "passive"))
    )
    (net (code "75") (name "Net-(MCP23017_1-GPA4)") (class "Default")
      (node (ref "MCP23017_1") (pin "25") (pinfunction "GPA4_25") (pintype "bidirectional"))
      (node (ref "R19") (pin "1") (pinfunction "1_1") (pintype "passive"))
    )
    (net (code "76") (name "Net-(MCP23017_1-GPA5)") (class "Default")
      (node (ref "MCP23017_1") (pin "26") (pinfunction "GPA5_26") (pintype "bidirectional"))
      (node (ref "R20") (pin "1") (pinfunction "1_1") (pintype "passive"))
    )
    (net (code "77") (name "Net-(MCP23017_1-GPA6)") (class "Default")
      (node (ref "MCP23017_1") (pin "27") (pinfunction "GPA6_27") (pintype "bidirectional"))
      (node (ref "R21") (pin "1") (pinfunction "1_1") (pintype "passive"))
    )
    (net (code "78") (name "Net-(MCP23017_1-GPA7)") (class "Default")
      (node (ref "MCP23017_1") (pin "28") (pinfunction "GPA7_28") (pintype "bidirectional"))
      (node (ref "R22") (pin "1") (pinfunction "1_1") (pintype "passive"))
    )
    (net (code "79") (name "Net-(MCP23017_1-GPB7)") (class "Default")
      (node (ref "MCP23017_1") (pin "8") (pinfunction "GPB7_8") (pintype "bidirectional"))
      (node (ref "R23") (pin "1") (pinfunction "1_1") (pintype "passive"))
    )
    (net (code "80") (name "Net-(MCP23017_1-~{RESET})") (class "Default")
      (node (ref "MCP23017_1") (pin "18") (pinfunction "~{RESET}_18") (pintype "input"))
      (node (ref "R35") (pin "2") (pinfunction "2_2") (pintype "passive"))
    )
    (net (code "81") (name "Net-(MCP23017_2-GPA0)") (class "Default")
      (node (ref "MCP23017_2") (pin "21") (pinfunction "GPA0_21") (pintype "bidirectional"))
      (node (ref "R4") (pin "1") (pinfunction "1_1") (pintype "passive"))
    )
    (net (code "82") (name "Net-(MCP23017_2-GPA1)") (class "Default")
      (node (ref "MCP23017_2") (pin "22") (pinfunction "GPA1_22") (pintype "bidirectional"))
      (node (ref "R5") (pin "1") (pinfunction "1_1") (pintype "passive"))
    )
    (net (code "83") (name "Net-(MCP23017_2-GPA2)") (class "Default")
      (node (ref "MCP23017_2") (pin "23") (pinfunction "GPA2_23") (pintype "bidirectional"))
      (node (ref "R6") (pin "1") (pinfunction "1_1") (pintype "passive"))
    )
    (net (code "84") (name "Net-(MCP23017_2-GPA3)") (class "Default")
      (node (ref "MCP23017_2") (pin "24") (pinfunction "GPA3_24") (pintype "bidirectional"))
      (node (ref "R7") (pin "1") (pinfunction "1_1") (pintype "passive"))
    )
    (net (code "85") (name "Net-(MCP23017_2-GPA4)") (class "Default")
      (node (ref "MCP23017_2") (pin "25") (pinfunction "GPA4_25") (pintype "bidirectional"))
      (node (ref "R8") (pin "1") (pinfunction "1_1") (pintype "passive"))
    )
    (net (code "86") (name "Net-(MCP23017_2-GPA5)") (class "Default")
      (node (ref "MCP23017_2") (pin "26") (pinfunction "GPA5_26") (pintype "bidirectional"))
      (node (ref "R9") (pin "1") (pinfunction "1_1") (pintype "passive"))
    )
    (net (code "87") (name "Net-(MCP23017_2-GPA6)") (class "Default")
      (node (ref "MCP23017_2") (pin "27") (pinfunction "GPA6_27") (pintype "bidirectional"))
      (node (ref "R10") (pin "1") (pinfunction "1_1") (pintype "passive"))
    )
    (net (code "88") (name "Net-(MCP23017_2-GPA7)") (class "Default")
      (node (ref "MCP23017_2") (pin "28") (pinfunction "GPA7_28") (pintype "bidirectional"))
      (node (ref "R11") (pin "1") (pinfunction "1_1") (pintype "passive"))
    )
    (net (code "89") (name "Net-(MCP23017_2-GPB0)") (class "Default")
      (node (ref "MCP23017_2") (pin "1") (pinfunction "GPB0_1") (pintype "bidirectional"))
      (node (ref "R1") (pin "1") (pinfunction "1_1") (pintype "passive"))
    )
    (net (code "90") (name "Net-(MCP23017_2-GPB1)") (class "Default")
      (node (ref "MCP23017_2") (pin "2") (pinfunction "GPB1_2") (pintype "bidirectional"))
      (node (ref "R2") (pin "1") (pinfunction "1_1") (pintype "passive"))
    )
    (net (code "91") (name "Net-(MCP23017_2-GPB2)") (class "Default")
      (node (ref "MCP23017_2") (pin "3") (pinfunction "GPB2_3") (pintype "bidirectional"))
      (node (ref "R3") (pin "1") (pinfunction "1_1") (pintype "passive"))
    )
    (net (code "92") (name "Net-(MCP23017_2-GPB7)") (class "Default")
      (node (ref "MCP23017_2") (pin "8") (pinfunction "GPB7_8") (pintype "bidirectional"))
      (node (ref "R12") (pin "1") (pinfunction "1_1") (pintype "passive"))
    )
    (net (code "93") (name "Net-(MCP23017_2-~{RESET})") (class "Default")
      (node (ref "MCP23017_2") (pin "18") (pinfunction "~{RESET}_18") (pintype "input"))
      (node (ref "R34") (pin "2") (pinfunction "2_2") (pintype "passive"))
    )
    (net (code "94") (name "unconnected-(ADX345--1-PadA1)") (class "Default")
      (node (ref "ADX345") (pin "A1") (pinfunction "-1_A1") (pintype "passive"))
    )
    (net (code "95") (name "unconnected-(ADX345--2-PadA2)") (class "Default")
      (node (ref "ADX345") (pin "A2") (pinfunction "-2_A2") (pintype "passive"))
    )
    (net (code "96") (name "unconnected-(ADX345--3-PadA3)") (class "Default")
      (node (ref "ADX345") (pin "A3") (pinfunction "-3_A3") (pintype "passive"))
    )
    (net (code "97") (name "unconnected-(ADX345--4-PadA4)") (class "Default")
      (node (ref "ADX345") (pin "A4") (pinfunction "-4_A4") (pintype "passive"))
    )
    (net (code "98") (name "unconnected-(FRISCHWASSERTANK--1-PadA1)") (class "Default")
      (node (ref "FRISCHWASSERTANK") (pin "A1") (pinfunction "-1_A1") (pintype "passive"))
    )
    (net (code "99") (name "unconnected-(FRISCHWASSERTANK--2-PadA2)") (class "Default")
      (node (ref "FRISCHWASSERTANK") (pin "A2") (pinfunction "-2_A2") (pintype "passive"))
    )
    (net (code "100") (name "unconnected-(FRISCHWASSERTANK--3-PadA3)") (class "Default")
      (node (ref "FRISCHWASSERTANK") (pin "A3") (pinfunction "-3_A3") (pintype "passive"))
    )
    (net (code "101") (name "unconnected-(FRISCHWASSERTANK--4-PadA4)") (class "Default")
      (node (ref "FRISCHWASSERTANK") (pin "A4") (pinfunction "-4_A4") (pintype "passive"))
    )
    (net (code "102") (name "unconnected-(FRISCHWASSERTANK--5-PadA5)") (class "Default")
      (node (ref "FRISCHWASSERTANK") (pin "A5") (pinfunction "-5_A5") (pintype "passive"))
    )
    (net (code "103") (name "unconnected-(FRISCHWASSERTANK--6-PadA6)") (class "Default")
      (node (ref "FRISCHWASSERTANK") (pin "A6") (pinfunction "-6_A6") (pintype "passive"))
    )
    (net (code "104") (name "unconnected-(FRISCHWASSERTANK--7-PadA7)") (class "Default")
      (node (ref "FRISCHWASSERTANK") (pin "A7") (pinfunction "-7_A7") (pintype "passive"))
    )
    (net (code "105") (name "unconnected-(FRISCHWASSERTANK--8-PadA8)") (class "Default")
      (node (ref "FRISCHWASSERTANK") (pin "A8") (pinfunction "-8_A8") (pintype "passive"))
    )
    (net (code "106") (name "unconnected-(FÄKALIENTANK--1-PadA1)") (class "Default")
      (node (ref "FÄKALIENTANK") (pin "A1") (pinfunction "-1_A1") (pintype "passive"))
    )
    (net (code "107") (name "unconnected-(FÄKALIENTANK--2-PadA2)") (class "Default")
      (node (ref "FÄKALIENTANK") (pin "A2") (pinfunction "-2_A2") (pintype "passive"))
    )
    (net (code "108") (name "unconnected-(FÄKALIENTANK--3-PadA3)") (class "Default")
      (node (ref "FÄKALIENTANK") (pin "A3") (pinfunction "-3_A3") (pintype "passive"))
    )
    (net (code "109") (name "unconnected-(FÄKALIENTANK--4-PadA4)") (class "Default")
      (node (ref "FÄKALIENTANK") (pin "A4") (pinfunction "-4_A4") (pintype "passive"))
    )
    (net (code "110") (name "unconnected-(FÄKALIENTANK--5-PadA5)") (class "Default")
      (node (ref "FÄKALIENTANK") (pin "A5") (pinfunction "-5_A5") (pintype "passive"))
    )
    (net (code "111") (name "unconnected-(FÄKALIENTANK--6-PadA6)") (class "Default")
      (node (ref "FÄKALIENTANK") (pin "A6") (pinfunction "-6_A6") (pintype "passive"))
    )
    (net (code "112") (name "unconnected-(FÄKALIENTANK--7-PadA7)") (class "Default")
      (node (ref "FÄKALIENTANK") (pin "A7") (pinfunction "-7_A7") (pintype "passive"))
    )
    (net (code "113") (name "unconnected-(FÄKALIENTANK--8-PadA8)") (class "Default")
      (node (ref "FÄKALIENTANK") (pin "A8") (pinfunction "-8_A8") (pintype "passive"))
    )
    (net (code "114") (name "unconnected-(FÄKALIENTANK-B-7-PadB7)") (class "Default")
      (node (ref "FÄKALIENTANK") (pin "B7") (pinfunction "B-7_B7") (pintype "passive"))
    )
    (net (code "115") (name "unconnected-(FÄKALIENTANK-B-8-PadB8)") (class "Default")
      (node (ref "FÄKALIENTANK") (pin "B8") (pinfunction "B-8_B8") (pintype "passive"))
    )
    (net (code "116") (name "unconnected-(GASWAAGE--1-PadA1)") (class "Default")
      (node (ref "GASWAAGE") (pin "A1") (pinfunction "-1_A1") (pintype "passive"))
    )
    (net (code "117") (name "unconnected-(GASWAAGE--2-PadA2)") (class "Default")
      (node (ref "GASWAAGE") (pin "A2") (pinfunction "-2_A2") (pintype "passive"))
    )
    (net (code "118") (name "unconnected-(GASWAAGE--3-PadA3)") (class "Default")
      (node (ref "GASWAAGE") (pin "A3") (pinfunction "-3_A3") (pintype "passive"))
    )
    (net (code "119") (name "unconnected-(GASWAAGE--4-PadA4)") (class "Default")
      (node (ref "GASWAAGE") (pin "A4") (pinfunction "-4_A4") (pintype "passive"))
    )
    (net (code "120") (name "unconnected-(GEHÄUSEDECKEL-Pad4)") (class "Default")
      (node (ref "GEHÄUSEDECKEL") (pin "4") (pinfunction "4_4") (pintype "passive"))
    )
    (net (code "121") (name "unconnected-(GEHÄUSEDECKEL-Pad6)") (class "Default")
      (node (ref "GEHÄUSEDECKEL") (pin "6") (pinfunction "6_6") (pintype "passive"))
    )
    (net (code "122") (name "unconnected-(GEHÄUSEDECKEL-Pad8)") (class "Default")
      (node (ref "GEHÄUSEDECKEL") (pin "8") (pinfunction "8_8") (pintype "passive"))
    )
    (net (code "123") (name "unconnected-(GEHÄUSEDECKEL-Pad10)") (class "Default")
      (node (ref "GEHÄUSEDECKEL") (pin "10") (pinfunction "10_10") (pintype "passive"))
    )
    (net (code "124") (name "unconnected-(GEHÄUSEDECKEL-Pad12)") (class "Default")
      (node (ref "GEHÄUSEDECKEL") (pin "12") (pinfunction "12_12") (pintype "passive"))
    )
    (net (code "125") (name "unconnected-(GPIO_EXTENSION--1-PadA1)") (class "Default")
      (node (ref "GPIO_EXTENSION") (pin "A1") (pinfunction "-1_A1") (pintype "passive"))
    )
    (net (code "126") (name "unconnected-(GPIO_EXTENSION--2-PadA2)") (class "Default")
      (node (ref "GPIO_EXTENSION") (pin "A2") (pinfunction "-2_A2") (pintype "passive"))
    )
    (net (code "127") (name "unconnected-(GPIO_EXTENSION--3-PadA3)") (class "Default")
      (node (ref "GPIO_EXTENSION") (pin "A3") (pinfunction "-3_A3") (pintype "passive"))
    )
    (net (code "128") (name "unconnected-(GPIO_EXTENSION--4-PadA4)") (class "Default")
      (node (ref "GPIO_EXTENSION") (pin "A4") (pinfunction "-4_A4") (pintype "passive"))
    )
    (net (code "129") (name "unconnected-(GPIO_EXTENSION--5-PadA5)") (class "Default")
      (node (ref "GPIO_EXTENSION") (pin "A5") (pinfunction "-5_A5") (pintype "passive"))
    )
    (net (code "130") (name "unconnected-(GPIO_EXTENSION--6-PadA6)") (class "Default")
      (node (ref "GPIO_EXTENSION") (pin "A6") (pinfunction "-6_A6") (pintype "passive"))
    )
    (net (code "131") (name "unconnected-(GPIO_EXTENSION--7-PadA7)") (class "Default")
      (node (ref "GPIO_EXTENSION") (pin "A7") (pinfunction "-7_A7") (pintype "passive"))
    )
    (net (code "132") (name "unconnected-(GPIO_EXTENSION--8-PadA8)") (class "Default")
      (node (ref "GPIO_EXTENSION") (pin "A8") (pinfunction "-8_A8") (pintype "passive"))
    )
    (net (code "133") (name "unconnected-(GPIO_EXTENSION--9-PadA9)") (class "Default")
      (node (ref "GPIO_EXTENSION") (pin "A9") (pinfunction "-9_A9") (pintype "passive"))
    )
    (net (code "134") (name "unconnected-(GPIO_EXTENSION--10-PadA10)") (class "Default")
      (node (ref "GPIO_EXTENSION") (pin "A10") (pinfunction "-10_A10") (pintype "passive"))
    )
    (net (code "135") (name "unconnected-(GPIO_EXTENSION--11-PadA11)") (class "Default")
      (node (ref "GPIO_EXTENSION") (pin "A11") (pinfunction "-11_A11") (pintype "passive"))
    )
    (net (code "136") (name "unconnected-(GPIO_EXTENSION--12-PadA12)") (class "Default")
      (node (ref "GPIO_EXTENSION") (pin "A12") (pinfunction "-12_A12") (pintype "passive"))
    )
    (net (code "137") (name "unconnected-(GPIO_EXTENSION--13-PadA13)") (class "Default")
      (node (ref "GPIO_EXTENSION") (pin "A13") (pinfunction "-13_A13") (pintype "passive"))
    )
    (net (code "138") (name "unconnected-(GPIO_EXTENSION--14-PadA14)") (class "Default")
      (node (ref "GPIO_EXTENSION") (pin "A14") (pinfunction "-14_A14") (pintype "passive"))
    )
    (net (code "139") (name "unconnected-(GPIO_EXTENSION--15-PadA15)") (class "Default")
      (node (ref "GPIO_EXTENSION") (pin "A15") (pinfunction "-15_A15") (pintype "passive"))
    )
    (net (code "140") (name "unconnected-(GPIO_EXTENSION--16-PadA16)") (class "Default")
      (node (ref "GPIO_EXTENSION") (pin "A16") (pinfunction "-16_A16") (pintype "passive"))
    )
    (net (code "141") (name "unconnected-(HX711-EXTERN--1-PadA1)") (class "Default")
      (node (ref "HX711-EXTERN") (pin "A1") (pinfunction "-1_A1") (pintype "passive"))
    )
    (net (code "142") (name "unconnected-(HX711-EXTERN--2-PadA2)") (class "Default")
      (node (ref "HX711-EXTERN") (pin "A2") (pinfunction "-2_A2") (pintype "passive"))
    )
    (net (code "143") (name "unconnected-(HX711-EXTERN--3-PadA3)") (class "Default")
      (node (ref "HX711-EXTERN") (pin "A3") (pinfunction "-3_A3") (pintype "passive"))
    )
    (net (code "144") (name "unconnected-(HX711-EXTERN--4-PadA4)") (class "Default")
      (node (ref "HX711-EXTERN") (pin "A4") (pinfunction "-4_A4") (pintype "passive"))
    )
    (net (code "145") (name "unconnected-(HX711-PadB+)") (class "Default")
      (node (ref "HX711") (pin "B+") (pinfunction "B+_B+") (pintype "bidirectional"))
    )
    (net (code "146") (name "unconnected-(HX711-PadB-)") (class "Default")
      (node (ref "HX711") (pin "B-") (pinfunction "B-_B-") (pintype "bidirectional"))
    )
    (net (code "147") (name "unconnected-(I2C-EXTENSION-Pad2)") (class "Default")
      (node (ref "I2C-EXTENSION") (pin "2") (pinfunction "2_2") (pintype "passive"))
    )
    (net (code "148") (name "unconnected-(I2C-EXTENSION-Pad4)") (class "Default")
      (node (ref "I2C-EXTENSION") (pin "4") (pinfunction "4_4") (pintype "passive"))
    )
    (net (code "149") (name "unconnected-(I2C-EXTENSION-Pad6)") (class "Default")
      (node (ref "I2C-EXTENSION") (pin "6") (pinfunction "6_6") (pintype "passive"))
    )
    (net (code "150") (name "unconnected-(I2C-EXTENSION-Pad7)") (class "Default")
      (node (ref "I2C-EXTENSION") (pin "7") (pinfunction "7_7") (pintype "passive"))
    )
    (net (code "151") (name "unconnected-(I2C-EXTENSION-Pad8)") (class "Default")
      (node (ref "I2C-EXTENSION") (pin "8") (pinfunction "8_8") (pintype "passive"))
    )
    (net (code "152") (name "unconnected-(I2CEXTENDER1-N.C.-Pad5)") (class "Default")
      (node (ref "I2CEXTENDER1") (pin "5") (pinfunction "N.C._5") (pintype "no_connect"))
    )
    (net (code "153") (name "unconnected-(I2CEXTENDER1-N.C._2-Pad1)") (class "Default")
      (node (ref "I2CEXTENDER1") (pin "1") (pinfunction "N.C._2_1") (pintype "no_connect"))
    )
    (net (code "154") (name "unconnected-(I2CEXTENDER2-N.C.-Pad5)") (class "Default")
      (node (ref "I2CEXTENDER2") (pin "5") (pinfunction "N.C._5") (pintype "no_connect"))
    )
    (net (code "155") (name "unconnected-(I2CEXTENDER2-N.C._2-Pad1)") (class "Default")
      (node (ref "I2CEXTENDER2") (pin "1") (pinfunction "N.C._2_1") (pintype "no_connect"))
    )
    (net (code "156") (name "unconnected-(KLIMA1--1-PadA1)") (class "Default")
      (node (ref "KLIMA1") (pin "A1") (pinfunction "-1_A1") (pintype "passive"))
    )
    (net (code "157") (name "unconnected-(KLIMA1--2-PadA2)") (class "Default")
      (node (ref "KLIMA1") (pin "A2") (pinfunction "-2_A2") (pintype "passive"))
    )
    (net (code "158") (name "unconnected-(KLIMA1--3-PadA3)") (class "Default")
      (node (ref "KLIMA1") (pin "A3") (pinfunction "-3_A3") (pintype "passive"))
    )
    (net (code "159") (name "unconnected-(KLIMA1--4-PadA4)") (class "Default")
      (node (ref "KLIMA1") (pin "A4") (pinfunction "-4_A4") (pintype "passive"))
    )
    (net (code "160") (name "unconnected-(KLIMA2--1-PadA1)") (class "Default")
      (node (ref "KLIMA2") (pin "A1") (pinfunction "-1_A1") (pintype "passive"))
    )
    (net (code "161") (name "unconnected-(KLIMA2--2-PadA2)") (class "Default")
      (node (ref "KLIMA2") (pin "A2") (pinfunction "-2_A2") (pintype "passive"))
    )
    (net (code "162") (name "unconnected-(KLIMA2--3-PadA3)") (class "Default")
      (node (ref "KLIMA2") (pin "A3") (pinfunction "-3_A3") (pintype "passive"))
    )
    (net (code "163") (name "unconnected-(KLIMA2--4-PadA4)") (class "Default")
      (node (ref "KLIMA2") (pin "A4") (pinfunction "-4_A4") (pintype "passive"))
    )
    (net (code "164") (name "unconnected-(KüHLSCHR.--1-PadA1)") (class "Default")
      (node (ref "KüHLSCHR.") (pin "A1") (pinfunction "-1_A1") (pintype "passive"))
    )
    (net (code "165") (name "unconnected-(KüHLSCHR.--2-PadA2)") (class "Default")
      (node (ref "KüHLSCHR.") (pin "A2") (pinfunction "-2_A2") (pintype "passive"))
    )
    (net (code "166") (name "unconnected-(KüHLSCHR.--3-PadA3)") (class "Default")
      (node (ref "KüHLSCHR.") (pin "A3") (pinfunction "-3_A3") (pintype "passive"))
    )
    (net (code "167") (name "unconnected-(LED-HL--1-PadA1)") (class "Default")
      (node (ref "LED-HL") (pin "A1") (pinfunction "-1_A1") (pintype "passive"))
    )
    (net (code "168") (name "unconnected-(LED-HL--2-PadA2)") (class "Default")
      (node (ref "LED-HL") (pin "A2") (pinfunction "-2_A2") (pintype "passive"))
    )
    (net (code "169") (name "unconnected-(LED-HL--3-PadA3)") (class "Default")
      (node (ref "LED-HL") (pin "A3") (pinfunction "-3_A3") (pintype "passive"))
    )
    (net (code "170") (name "unconnected-(LED-HL--4-PadA4)") (class "Default")
      (node (ref "LED-HL") (pin "A4") (pinfunction "-4_A4") (pintype "passive"))
    )
    (net (code "171") (name "unconnected-(LED-HR--1-PadA1)") (class "Default")
      (node (ref "LED-HR") (pin "A1") (pinfunction "-1_A1") (pintype "passive"))
    )
    (net (code "172") (name "unconnected-(LED-HR--2-PadA2)") (class "Default")
      (node (ref "LED-HR") (pin "A2") (pinfunction "-2_A2") (pintype "passive"))
    )
    (net (code "173") (name "unconnected-(LED-HR--3-PadA3)") (class "Default")
      (node (ref "LED-HR") (pin "A3") (pinfunction "-3_A3") (pintype "passive"))
    )
    (net (code "174") (name "unconnected-(LED-HR--4-PadA4)") (class "Default")
      (node (ref "LED-HR") (pin "A4") (pinfunction "-4_A4") (pintype "passive"))
    )
    (net (code "175") (name "unconnected-(LED-VD--1-PadA1)") (class "Default")
      (node (ref "LED-VD") (pin "A1") (pinfunction "-1_A1") (pintype "passive"))
    )
    (net (code "176") (name "unconnected-(LED-VD--2-PadA2)") (class "Default")
      (node (ref "LED-VD") (pin "A2") (pinfunction "-2_A2") (pintype "passive"))
    )
    (net (code "177") (name "unconnected-(LED-VD--3-PadA3)") (class "Default")
      (node (ref "LED-VD") (pin "A3") (pinfunction "-3_A3") (pintype "passive"))
    )
    (net (code "178") (name "unconnected-(LED-VD--4-PadA4)") (class "Default")
      (node (ref "LED-VD") (pin "A4") (pinfunction "-4_A4") (pintype "passive"))
    )
    (net (code "179") (name "unconnected-(LED-VL--1-PadA1)") (class "Default")
      (node (ref "LED-VL") (pin "A1") (pinfunction "-1_A1") (pintype "passive"))
    )
    (net (code "180") (name "unconnected-(LED-VL--2-PadA2)") (class "Default")
      (node (ref "LED-VL") (pin "A2") (pinfunction "-2_A2") (pintype "passive"))
    )
    (net (code "181") (name "unconnected-(LED-VL--3-PadA3)") (class "Default")
      (node (ref "LED-VL") (pin "A3") (pinfunction "-3_A3") (pintype "passive"))
    )
    (net (code "182") (name "unconnected-(LED-VL--4-PadA4)") (class "Default")
      (node (ref "LED-VL") (pin "A4") (pinfunction "-4_A4") (pintype "passive"))
    )
    (net (code "183") (name "unconnected-(LED-VR--1-PadA1)") (class "Default")
      (node (ref "LED-VR") (pin "A1") (pinfunction "-1_A1") (pintype "passive"))
    )
    (net (code "184") (name "unconnected-(LED-VR--2-PadA2)") (class "Default")
      (node (ref "LED-VR") (pin "A2") (pinfunction "-2_A2") (pintype "passive"))
    )
    (net (code "185") (name "unconnected-(LED-VR--3-PadA3)") (class "Default")
      (node (ref "LED-VR") (pin "A3") (pinfunction "-3_A3") (pintype "passive"))
    )
    (net (code "186") (name "unconnected-(LED-VR--4-PadA4)") (class "Default")
      (node (ref "LED-VR") (pin "A4") (pinfunction "-4_A4") (pintype "passive"))
    )
    (net (code "187") (name "unconnected-(LED-ZL--1-PadA1)") (class "Default")
      (node (ref "LED-ZL") (pin "A1") (pinfunction "-1_A1") (pintype "passive"))
    )
    (net (code "188") (name "unconnected-(LED-ZL--2-PadA2)") (class "Default")
      (node (ref "LED-ZL") (pin "A2") (pinfunction "-2_A2") (pintype "passive"))
    )
    (net (code "189") (name "unconnected-(LED-ZL--3-PadA3)") (class "Default")
      (node (ref "LED-ZL") (pin "A3") (pinfunction "-3_A3") (pintype "passive"))
    )
    (net (code "190") (name "unconnected-(LED-ZL--4-PadA4)") (class "Default")
      (node (ref "LED-ZL") (pin "A4") (pinfunction "-4_A4") (pintype "passive"))
    )
    (net (code "191") (name "unconnected-(LED-ZR--1-PadA1)") (class "Default")
      (node (ref "LED-ZR") (pin "A1") (pinfunction "-1_A1") (pintype "passive"))
    )
    (net (code "192") (name "unconnected-(LED-ZR--2-PadA2)") (class "Default")
      (node (ref "LED-ZR") (pin "A2") (pinfunction "-2_A2") (pintype "passive"))
    )
    (net (code "193") (name "unconnected-(LED-ZR--3-PadA3)") (class "Default")
      (node (ref "LED-ZR") (pin "A3") (pinfunction "-3_A3") (pintype "passive"))
    )
    (net (code "194") (name "unconnected-(LED-ZR--4-PadA4)") (class "Default")
      (node (ref "LED-ZR") (pin "A4") (pinfunction "-4_A4") (pintype "passive"))
    )
    (net (code "195") (name "unconnected-(MCP23017_1-INTA-Pad20)") (class "Default")
      (node (ref "MCP23017_1") (pin "20") (pinfunction "INTA_20") (pintype "output"))
    )
    (net (code "196") (name "unconnected-(MCP23017_1-INTB-Pad19)") (class "Default")
      (node (ref "MCP23017_1") (pin "19") (pinfunction "INTB_19") (pintype "output"))
    )
    (net (code "197") (name "unconnected-(MCP23017_2-INTA-Pad20)") (class "Default")
      (node (ref "MCP23017_2") (pin "20") (pinfunction "INTA_20") (pintype "output"))
    )
    (net (code "198") (name "unconnected-(MCP23017_2-INTB-Pad19)") (class "Default")
      (node (ref "MCP23017_2") (pin "19") (pinfunction "INTB_19") (pintype "output"))
    )
    (net (code "199") (name "unconnected-(RADAR--1-PadA1)") (class "Default")
      (node (ref "RADAR") (pin "A1") (pinfunction "-1_A1") (pintype "passive"))
    )
    (net (code "200") (name "unconnected-(RADAR--2-PadA2)") (class "Default")
      (node (ref "RADAR") (pin "A2") (pinfunction "-2_A2") (pintype "passive"))
    )
    (net (code "201") (name "unconnected-(RADAR--3-PadA3)") (class "Default")
      (node (ref "RADAR") (pin "A3") (pinfunction "-3_A3") (pintype "passive"))
    )
    (net (code "202") (name "unconnected-(RASPBERRY-PI-Pad10)") (class "Default")
      (node (ref "RASPBERRY-PI") (pin "10") (pinfunction "10_10") (pintype "passive"))
    )
  )
)
